# modFOC-Power_Module.net
KiCad netlist of a schematic drawn in Altium Designer
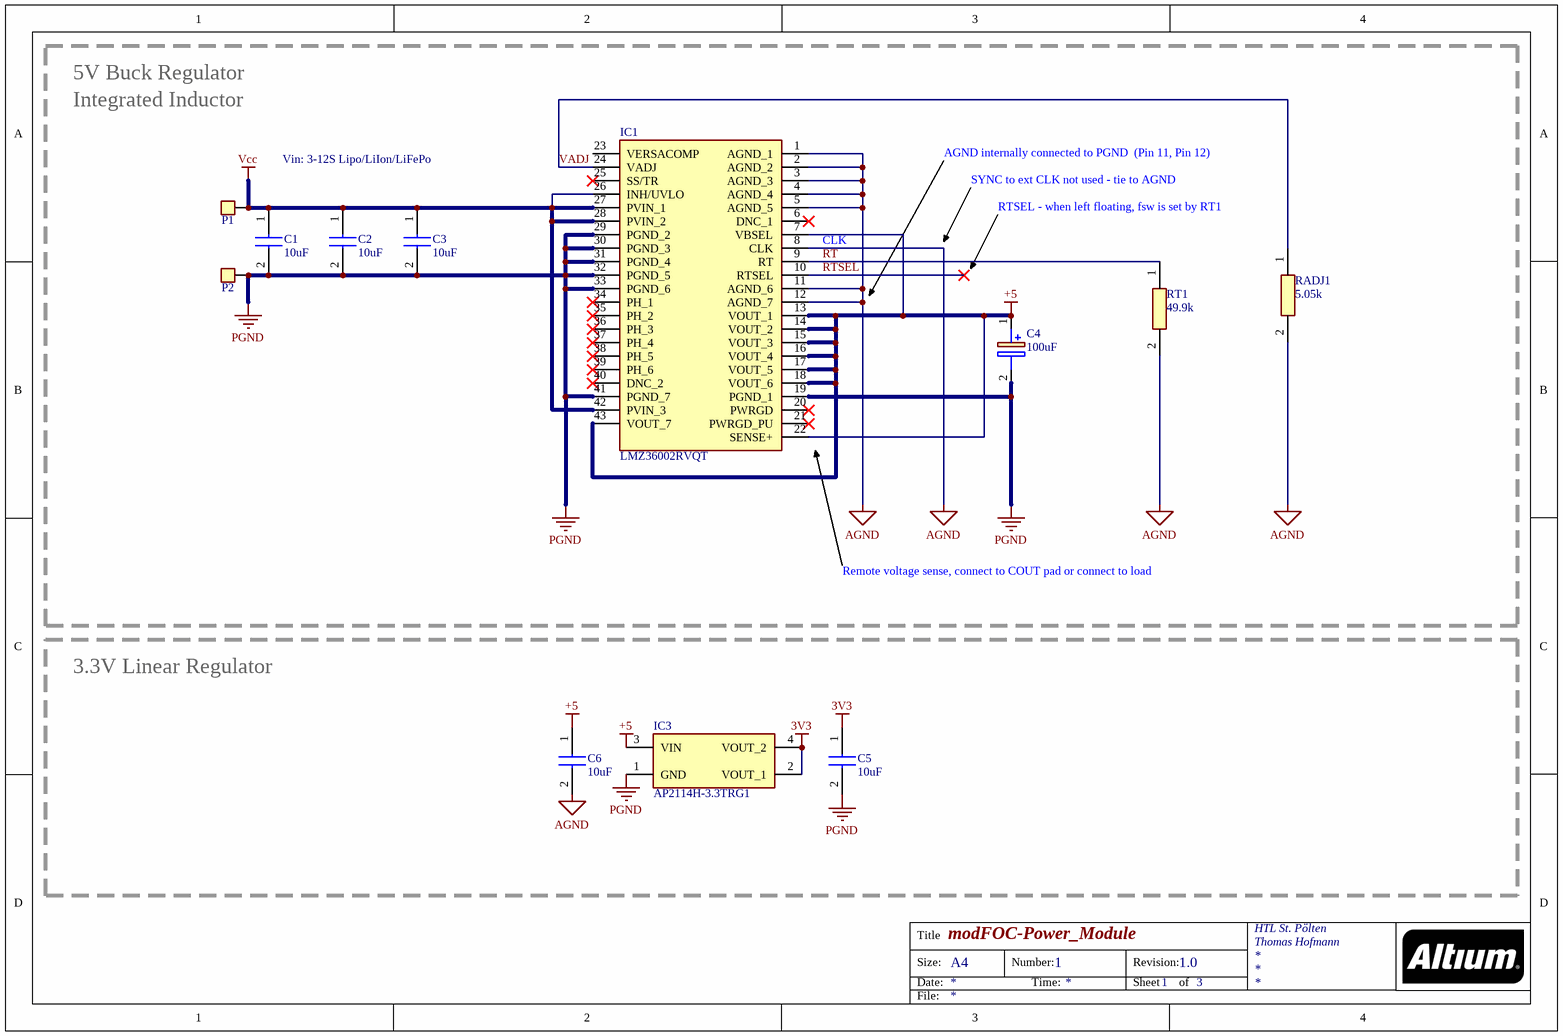
[diagram p0: modFOC-Power_Module.SchDoc]

(export (version "E")
  (design (tool "Eeschema 10.0.6"))
  (components
    (comp (ref "C1")
      (value "10uF")
      (footprint "RcMPPTLib:CAPC3225X280N")
      (description "Capacitor")
      (fields (field (name "MANUFACTURER_PART_NUMBER") "CL32B106KMVNNWE"))
      (libsource (lib "RcMPPTLib") (part "CL32B106KMVNNWE"))
    )
    (comp (ref "C2")
      (value "10uF")
      (footprint "RcMPPTLib:CAPC3225X280N")
      (description "Capacitor")
      (fields (field (name "MANUFACTURER_PART_NUMBER") "CL32B106KMVNNWE"))
      (libsource (lib "RcMPPTLib") (part "CL32B106KMVNNWE"))
    )
    (comp (ref "C3")
      (value "10uF")
      (footprint "RcMPPTLib:CAPC3225X280N")
      (description "Capacitor")
      (fields (field (name "MANUFACTURER_PART_NUMBER") "CL32B106KMVNNWE"))
      (libsource (lib "RcMPPTLib") (part "CL32B106KMVNNWE"))
    )
    (comp (ref "C4")
      (value "100uF")
      (footprint "CAPPM3528X200N")
      (description "Capacitor Polarised")
      (fields
        (field (name "MANUFACTURER_PART_NUMBER") "8TPE100MAZB")
        (field (name "MOUSER PART NUMBER") "667-8TPE100MAZB")
      )
      (libsource (lib "RcMPPTLib") (part "8TPE100MAZB"))
    )
    (comp (ref "C5")
      (value "10uF")
      (footprint "RcMPPTLib:CAPC3225X280N")
      (description "Capacitor")
      (fields (field (name "MANUFACTURER_PART_NUMBER") "CL32B106KMVNNWE"))
      (libsource (lib "RcMPPTLib") (part "CL32B106KMVNNWE"))
    )
    (comp (ref "C6")
      (value "10uF")
      (footprint "RcMPPTLib:CAPC3225X280N")
      (description "Capacitor")
      (fields (field (name "MANUFACTURER_PART_NUMBER") "CL32B106KMVNNWE"))
      (libsource (lib "RcMPPTLib") (part "CL32B106KMVNNWE"))
    )
    (comp (ref "IC1")
      (value "LMZ36002RVQT")
      (footprint "LMZ36002RVQR")
      (description "Integrated Circuit")
      (fields (field (name "MOUSER PART NUMBER") "595-LMZ36002RVQT"))
      (libsource (lib "RcMPPTLib") (part "LMZ36002RVQT"))
    )
    (comp (ref "IC3")
      (value "AP2114H-3.3TRG1")
      (footprint "SOT230P700X180-4N")
      (description "Integrated Circuit")
      (fields (field (name "MOUSER PART NUMBER") "621-AP2114H-3.3TRG1"))
      (libsource (lib "RcMPPTLib") (part "AP2114H-3.3TRG1"))
    )
    (comp (ref "P1")
      (value "PowerPad")
      (footprint "POWER_PAD_S")
      (libsource (lib "RcMPPTLib") (part "PowerPad"))
    )
    (comp (ref "P2")
      (value "PowerPad")
      (footprint "POWER_PAD_S")
      (libsource (lib "RcMPPTLib") (part "PowerPad"))
    )
    (comp (ref "RADJ1")
      (value "5.05k")
      (footprint "R0805")
      (description "Resistor")
      (fields
        (field (name "MANUFACTURER_PART_NUMBER") "RT0805BRD075K05L")
        (field (name "MOUSER PART NUMBER") "603-RT0805BRD075K05L")
      )
      (libsource (lib "RcMPPTLib") (part "RT0805BRD075K05L"))
    )
    (comp (ref "RT1")
      (value "49.9k")
      (footprint "RcMPPTLib:R0805")
      (description "Resistor")
      (fields
        (field (name "MANUFACTURER_PART_NUMBER") "ERJ-6ENF4992V")
        (field (name "MOUSER PART NUMBER") "667-ERJ-6ENF4992V")
      )
      (libsource (lib "RcMPPTLib") (part "ERJ-6ENF4992V"))
    )
  )
  (nets
    (net (code "1") (name "+5") (class "Default")
      (node (ref "C4") (pin "1") (pinfunction "+_1") (pintype "passive"))
      (node (ref "C6") (pin "1") (pinfunction "1_1") (pintype "passive"))
      (node (ref "IC1") (pin "13") (pinfunction "VOUT_1_13") (pintype "passive"))
      (node (ref "IC1") (pin "14") (pinfunction "VOUT_2_14") (pintype "passive"))
      (node (ref "IC1") (pin "15") (pinfunction "VOUT_3_15") (pintype "passive"))
      (node (ref "IC1") (pin "16") (pinfunction "VOUT_4_16") (pintype "passive"))
      (node (ref "IC1") (pin "17") (pinfunction "VOUT_5_17") (pintype "passive"))
      (node (ref "IC1") (pin "18") (pinfunction "VOUT_6_18") (pintype "passive"))
      (node (ref "IC1") (pin "22") (pinfunction "SENSE+_22") (pintype "passive"))
      (node (ref "IC1") (pin "43") (pinfunction "VOUT_7_43") (pintype "passive"))
      (node (ref "IC1") (pin "7") (pinfunction "VBSEL_7") (pintype "passive"))
      (node (ref "IC3") (pin "3") (pinfunction "VIN_3") (pintype "passive"))
    )
    (net (code "2") (name "/RT") (class "Default")
      (node (ref "IC1") (pin "9") (pinfunction "RT_9") (pintype "passive"))
      (node (ref "RT1") (pin "1") (pinfunction "1_1") (pintype "passive"))
    )
    (net (code "3") (name "/RTSEL") (class "Default")
      (node (ref "IC1") (pin "10") (pinfunction "RTSEL_10") (pintype "passive+no_connect"))
    )
    (net (code "4") (name "/VADJ") (class "Default")
      (node (ref "IC1") (pin "24") (pinfunction "VADJ_24") (pintype "passive"))
      (node (ref "RADJ1") (pin "1") (pinfunction "1_1") (pintype "passive"))
    )
    (net (code "5") (name "3V3") (class "Default")
      (node (ref "C5") (pin "1") (pinfunction "1_1") (pintype "passive"))
      (node (ref "IC3") (pin "2") (pinfunction "VOUT_1_2") (pintype "passive"))
      (node (ref "IC3") (pin "4") (pinfunction "VOUT_2_4") (pintype "passive"))
    )
    (net (code "6") (name "AGND") (class "Default")
      (node (ref "C6") (pin "2") (pinfunction "2_2") (pintype "passive"))
      (node (ref "IC1") (pin "1") (pinfunction "AGND_1_1") (pintype "passive"))
      (node (ref "IC1") (pin "11") (pinfunction "AGND_6_11") (pintype "passive"))
      (node (ref "IC1") (pin "12") (pinfunction "AGND_7_12") (pintype "passive"))
      (node (ref "IC1") (pin "2") (pinfunction "AGND_2_2") (pintype "passive"))
      (node (ref "IC1") (pin "3") (pinfunction "AGND_3_3") (pintype "passive"))
      (node (ref "IC1") (pin "4") (pinfunction "AGND_4_4") (pintype "passive"))
      (node (ref "IC1") (pin "5") (pinfunction "AGND_5_5") (pintype "passive"))
      (node (ref "IC1") (pin "8") (pinfunction "CLK_8") (pintype "passive"))
      (node (ref "RADJ1") (pin "2") (pinfunction "2_2") (pintype "passive"))
      (node (ref "RT1") (pin "2") (pinfunction "2_2") (pintype "passive"))
    )
    (net (code "7") (name "PGND") (class "Default")
      (node (ref "C1") (pin "2") (pinfunction "2_2") (pintype "passive"))
      (node (ref "C2") (pin "2") (pinfunction "2_2") (pintype "passive"))
      (node (ref "C3") (pin "2") (pinfunction "2_2") (pintype "passive"))
      (node (ref "C4") (pin "2") (pinfunction "-_2") (pintype "passive"))
      (node (ref "C5") (pin "2") (pinfunction "2_2") (pintype "passive"))
      (node (ref "IC1") (pin "19") (pinfunction "PGND_1_19") (pintype "passive"))
      (node (ref "IC1") (pin "29") (pinfunction "PGND_2_29") (pintype "passive"))
      (node (ref "IC1") (pin "30") (pinfunction "PGND_3_30") (pintype "passive"))
      (node (ref "IC1") (pin "31") (pinfunction "PGND_4_31") (pintype "passive"))
      (node (ref "IC1") (pin "32") (pinfunction "PGND_5_32") (pintype "passive"))
      (node (ref "IC1") (pin "33") (pinfunction "PGND_6_33") (pintype "passive"))
      (node (ref "IC1") (pin "41") (pinfunction "PGND_7_41") (pintype "passive"))
      (node (ref "IC3") (pin "1") (pinfunction "GND_1") (pintype "passive"))
      (node (ref "P2") (pin "1") (pinfunction "1_1") (pintype "passive"))
    )
    (net (code "8") (name "Vcc") (class "Default")
      (node (ref "C1") (pin "1") (pinfunction "1_1") (pintype "passive"))
      (node (ref "C2") (pin "1") (pinfunction "1_1") (pintype "passive"))
      (node (ref "C3") (pin "1") (pinfunction "1_1") (pintype "passive"))
      (node (ref "IC1") (pin "26") (pinfunction "INH/UVLO_26") (pintype "passive"))
      (node (ref "IC1") (pin "27") (pinfunction "PVIN_1_27") (pintype "passive"))
      (node (ref "IC1") (pin "28") (pinfunction "PVIN_2_28") (pintype "passive"))
      (node (ref "IC1") (pin "42") (pinfunction "PVIN_3_42") (pintype "passive"))
      (node (ref "P1") (pin "1") (pinfunction "1_1") (pintype "passive"))
    )
    (net (code "9") (name "unconnected-(IC1-DNC_1-Pad6)") (class "Default")
      (node (ref "IC1") (pin "6") (pinfunction "DNC_1_6") (pintype "passive+no_connect"))
    )
    (net (code "10") (name "unconnected-(IC1-DNC_2-Pad40)") (class "Default")
      (node (ref "IC1") (pin "40") (pinfunction "DNC_2_40") (pintype "passive+no_connect"))
    )
    (net (code "11") (name "unconnected-(IC1-PH_1-Pad34)") (class "Default")
      (node (ref "IC1") (pin "34") (pinfunction "PH_1_34") (pintype "passive+no_connect"))
    )
    (net (code "12") (name "unconnected-(IC1-PH_2-Pad35)") (class "Default")
      (node (ref "IC1") (pin "35") (pinfunction "PH_2_35") (pintype "passive+no_connect"))
    )
    (net (code "13") (name "unconnected-(IC1-PH_3-Pad36)") (class "Default")
      (node (ref "IC1") (pin "36") (pinfunction "PH_3_36") (pintype "passive+no_connect"))
    )
    (net (code "14") (name "unconnected-(IC1-PH_4-Pad37)") (class "Default")
      (node (ref "IC1") (pin "37") (pinfunction "PH_4_37") (pintype "passive+no_connect"))
    )
    (net (code "15") (name "unconnected-(IC1-PH_5-Pad38)") (class "Default")
      (node (ref "IC1") (pin "38") (pinfunction "PH_5_38") (pintype "passive+no_connect"))
    )
    (net (code "16") (name "unconnected-(IC1-PH_6-Pad39)") (class "Default")
      (node (ref "IC1") (pin "39") (pinfunction "PH_6_39") (pintype "passive+no_connect"))
    )
    (net (code "17") (name "unconnected-(IC1-PWRGD-Pad20)") (class "Default")
      (node (ref "IC1") (pin "20") (pinfunction "PWRGD_20") (pintype "passive+no_connect"))
    )
    (net (code "18") (name "unconnected-(IC1-PWRGD_PU-Pad21)") (class "Default")
      (node (ref "IC1") (pin "21") (pinfunction "PWRGD_PU_21") (pintype "passive+no_connect"))
    )
    (net (code "19") (name "unconnected-(IC1-SS{slash}TR-Pad25)") (class "Default")
      (node (ref "IC1") (pin "25") (pinfunction "SS/TR_25") (pintype "passive+no_connect"))
    )
    (net (code "20") (name "unconnected-(IC1-VERSACOMP-Pad23)") (class "Default")
      (node (ref "IC1") (pin "23") (pinfunction "VERSACOMP_23") (pintype "passive"))
    )
  )
)
